# Sheet_HTN.net
KiCad netlist of a schematic drawn in Altium Designer
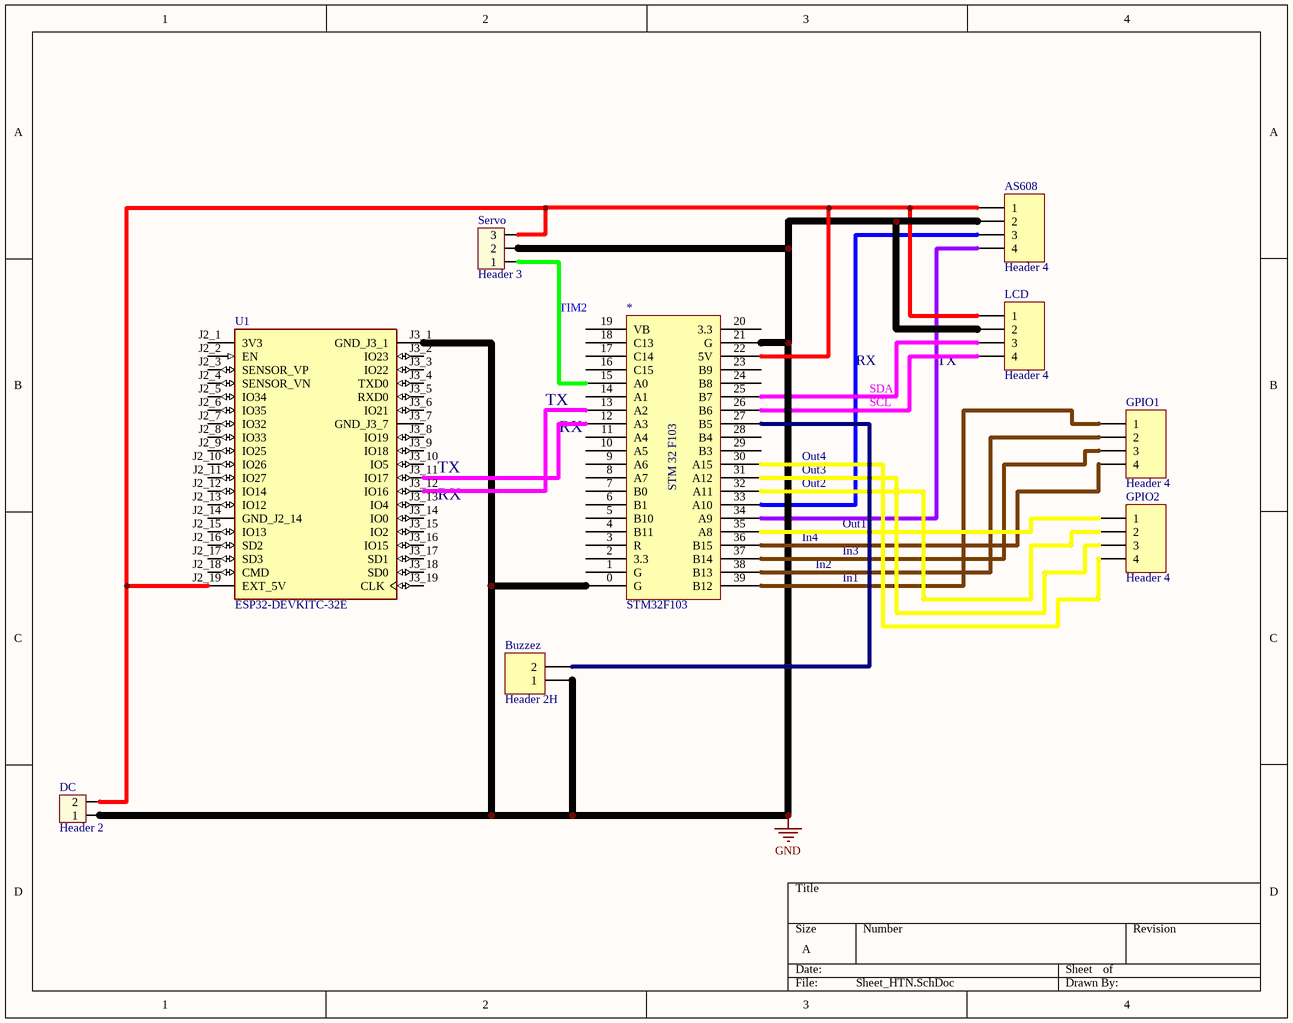
[diagram p0: Sheet_HTN.SchDoc]

(export (version "E")
  (design (tool "Eeschema 10.0.6"))
  (components
    (comp (ref "*")
      (value "STM32F103")
      (footprint "STM32F103")
      (libsource (lib "syhaunguyen__1") (part "STM32F103"))
    )
    (comp (ref "AS608")
      (value "Header 4")
      (footprint "HDR1X4")
      (description "Header, 4-Pin")
      (fields (field (name "PUBLISHER") "Altium Limited"))
      (libsource (lib "minhha") (part "Header 4"))
    )
    (comp (ref "Buzzez")
      (value "Header 2H")
      (footprint "HDR1X2H")
      (description "Header, 2-Pin, Right Angle")
      (fields (field (name "PUBLISHER") "Altium Limited"))
      (libsource (lib "minhha") (part "Header 2H"))
    )
    (comp (ref "DC")
      (value "Header 2")
      (footprint "HED2")
      (description "Header 2 (Green)")
      (libsource (lib "syhaunguyen") (part "Hed2"))
    )
    (comp (ref "GPIO1")
      (value "Header 4")
      (footprint "HDR1X4")
      (description "Header, 4-Pin")
      (fields (field (name "PUBLISHER") "Altium Limited"))
      (libsource (lib "minhha") (part "Header 4"))
    )
    (comp (ref "GPIO2")
      (value "Header 4")
      (footprint "HDR1X4")
      (description "Header, 4-Pin")
      (fields (field (name "PUBLISHER") "Altium Limited"))
      (libsource (lib "minhha") (part "Header 4"))
    )
    (comp (ref "LCD")
      (value "Header 4")
      (footprint "HDR1X4")
      (description "Header, 4-Pin")
      (fields (field (name "PUBLISHER") "Altium Limited"))
      (libsource (lib "minhha") (part "Header 4"))
    )
    (comp (ref "Servo")
      (value "Header 3")
      (footprint "HED3")
      (description "Header 3 (Green)")
      (libsource (lib "syhaunguyen") (part "Hed3"))
    )
    (comp (ref "U1")
      (value "ESP32-DEVKITC-32E")
      (footprint "MODULE_ESP32-DEVKITC-32E")
      (fields (field (name "MF") "Espressif Systems"))
      (libsource (lib "ESP32-DEVKITC-32E") (part "ESP32-DEVKITC-32E"))
    )
  )
  (nets
    (net (code "1") (name "GND") (class "Default")
      (node (ref "*") (pin "0") (pinfunction "G_0") (pintype "passive"))
      (node (ref "*") (pin "21") (pinfunction "G_21") (pintype "passive"))
      (node (ref "AS608") (pin "2") (pinfunction "2_2") (pintype "passive"))
      (node (ref "Buzzez") (pin "1") (pinfunction "1_1") (pintype "passive"))
      (node (ref "DC") (pin "1") (pinfunction "1_1") (pintype "passive"))
      (node (ref "LCD") (pin "2") (pinfunction "2_2") (pintype "passive"))
      (node (ref "Servo") (pin "2") (pinfunction "2_2") (pintype "passive"))
      (node (ref "U1") (pin "J3_1") (pinfunction "GND_J3_1_J3_1") (pintype "power_in"))
    )
    (net (code "2") (name "Net-(*-5V)") (class "Default")
      (node (ref "*") (pin "22") (pinfunction "5V_22") (pintype "passive"))
      (node (ref "AS608") (pin "1") (pinfunction "1_1") (pintype "passive"))
      (node (ref "DC") (pin "2") (pinfunction "2_2") (pintype "passive"))
      (node (ref "LCD") (pin "1") (pinfunction "1_1") (pintype "passive"))
      (node (ref "Servo") (pin "3") (pinfunction "3_3") (pintype "passive"))
      (node (ref "U1") (pin "J2_19") (pinfunction "EXT_5V_J2_19") (pintype "power_in"))
    )
    (net (code "3") (name "Net-(*-A0)") (class "Default")
      (node (ref "*") (pin "15") (pinfunction "A0_15") (pintype "passive"))
      (node (ref "Servo") (pin "1") (pinfunction "1_1") (pintype "passive"))
    )
    (net (code "4") (name "Net-(*-A2)") (class "Default")
      (node (ref "*") (pin "13") (pinfunction "A2_13") (pintype "passive"))
      (node (ref "U1") (pin "J3_12") (pinfunction "IO16_J3_12") (pintype "bidirectional"))
    )
    (net (code "5") (name "Net-(*-A3)") (class "Default")
      (node (ref "*") (pin "12") (pinfunction "A3_12") (pintype "passive"))
      (node (ref "U1") (pin "J3_11") (pinfunction "IO17_J3_11") (pintype "bidirectional"))
    )
    (net (code "6") (name "Net-(*-A8)") (class "Default")
      (node (ref "*") (pin "35") (pinfunction "A8_35") (pintype "passive"))
      (node (ref "GPIO2") (pin "1") (pinfunction "1_1") (pintype "passive"))
    )
    (net (code "7") (name "Net-(*-A9)") (class "Default")
      (node (ref "*") (pin "34") (pinfunction "A9_34") (pintype "passive"))
      (node (ref "AS608") (pin "4") (pinfunction "4_4") (pintype "passive"))
    )
    (net (code "8") (name "Net-(*-A10)") (class "Default")
      (node (ref "*") (pin "33") (pinfunction "A10_33") (pintype "passive"))
      (node (ref "AS608") (pin "3") (pinfunction "3_3") (pintype "passive"))
    )
    (net (code "9") (name "Net-(*-A11)") (class "Default")
      (node (ref "*") (pin "32") (pinfunction "A11_32") (pintype "passive"))
      (node (ref "GPIO2") (pin "2") (pinfunction "2_2") (pintype "passive"))
    )
    (net (code "10") (name "Net-(*-A12)") (class "Default")
      (node (ref "*") (pin "31") (pinfunction "A12_31") (pintype "passive"))
      (node (ref "GPIO2") (pin "3") (pinfunction "3_3") (pintype "passive"))
    )
    (net (code "11") (name "Net-(*-A15)") (class "Default")
      (node (ref "*") (pin "30") (pinfunction "A15_30") (pintype "passive"))
      (node (ref "GPIO2") (pin "4") (pinfunction "4_4") (pintype "passive"))
    )
    (net (code "12") (name "Net-(*-B5)") (class "Default")
      (node (ref "*") (pin "27") (pinfunction "B5_27") (pintype "passive"))
      (node (ref "Buzzez") (pin "2") (pinfunction "2_2") (pintype "passive"))
    )
    (net (code "13") (name "Net-(*-B6)") (class "Default")
      (node (ref "*") (pin "26") (pinfunction "B6_26") (pintype "passive"))
      (node (ref "LCD") (pin "4") (pinfunction "4_4") (pintype "passive"))
    )
    (net (code "14") (name "Net-(*-B7)") (class "Default")
      (node (ref "*") (pin "25") (pinfunction "B7_25") (pintype "passive"))
      (node (ref "LCD") (pin "3") (pinfunction "3_3") (pintype "passive"))
    )
    (net (code "15") (name "Net-(*-B12)") (class "Default")
      (node (ref "*") (pin "39") (pinfunction "B12_39") (pintype "passive"))
      (node (ref "GPIO1") (pin "1") (pinfunction "1_1") (pintype "passive"))
    )
    (net (code "16") (name "Net-(*-B13)") (class "Default")
      (node (ref "*") (pin "38") (pinfunction "B13_38") (pintype "passive"))
      (node (ref "GPIO1") (pin "2") (pinfunction "2_2") (pintype "passive"))
    )
    (net (code "17") (name "Net-(*-B14)") (class "Default")
      (node (ref "*") (pin "37") (pinfunction "B14_37") (pintype "passive"))
      (node (ref "GPIO1") (pin "3") (pinfunction "3_3") (pintype "passive"))
    )
    (net (code "18") (name "Net-(*-B15)") (class "Default")
      (node (ref "*") (pin "36") (pinfunction "B15_36") (pintype "passive"))
      (node (ref "GPIO1") (pin "4") (pinfunction "4_4") (pintype "passive"))
    )
    (net (code "19") (name "unconnected-(*-3.3-Pad2)") (class "Default")
      (node (ref "*") (pin "2") (pinfunction "3.3_2") (pintype "passive"))
    )
    (net (code "20") (name "unconnected-(*-3.3-Pad20)") (class "Default")
      (node (ref "*") (pin "20") (pinfunction "3.3_20") (pintype "passive"))
    )
    (net (code "21") (name "unconnected-(*-A1-Pad14)") (class "Default")
      (node (ref "*") (pin "14") (pinfunction "A1_14") (pintype "passive"))
    )
    (net (code "22") (name "unconnected-(*-A4-Pad11)") (class "Default")
      (node (ref "*") (pin "11") (pinfunction "A4_11") (pintype "passive"))
    )
    (net (code "23") (name "unconnected-(*-A5-Pad10)") (class "Default")
      (node (ref "*") (pin "10") (pinfunction "A5_10") (pintype "passive"))
    )
    (net (code "24") (name "unconnected-(*-A6-Pad9)") (class "Default")
      (node (ref "*") (pin "9") (pinfunction "A6_9") (pintype "passive"))
    )
    (net (code "25") (name "unconnected-(*-A7-Pad8)") (class "Default")
      (node (ref "*") (pin "8") (pinfunction "A7_8") (pintype "passive"))
    )
    (net (code "26") (name "unconnected-(*-B0-Pad7)") (class "Default")
      (node (ref "*") (pin "7") (pinfunction "B0_7") (pintype "passive"))
    )
    (net (code "27") (name "unconnected-(*-B1-Pad6)") (class "Default")
      (node (ref "*") (pin "6") (pinfunction "B1_6") (pintype "passive"))
    )
    (net (code "28") (name "unconnected-(*-B3-Pad29)") (class "Default")
      (node (ref "*") (pin "29") (pinfunction "B3_29") (pintype "passive"))
    )
    (net (code "29") (name "unconnected-(*-B4-Pad28)") (class "Default")
      (node (ref "*") (pin "28") (pinfunction "B4_28") (pintype "passive"))
    )
    (net (code "30") (name "unconnected-(*-B8-Pad24)") (class "Default")
      (node (ref "*") (pin "24") (pinfunction "B8_24") (pintype "passive"))
    )
    (net (code "31") (name "unconnected-(*-B9-Pad23)") (class "Default")
      (node (ref "*") (pin "23") (pinfunction "B9_23") (pintype "passive"))
    )
    (net (code "32") (name "unconnected-(*-B10-Pad5)") (class "Default")
      (node (ref "*") (pin "5") (pinfunction "B10_5") (pintype "passive"))
    )
    (net (code "33") (name "unconnected-(*-B11-Pad4)") (class "Default")
      (node (ref "*") (pin "4") (pinfunction "B11_4") (pintype "passive"))
    )
    (net (code "34") (name "unconnected-(*-C13-Pad18)") (class "Default")
      (node (ref "*") (pin "18") (pinfunction "C13_18") (pintype "passive"))
    )
    (net (code "35") (name "unconnected-(*-C14-Pad17)") (class "Default")
      (node (ref "*") (pin "17") (pinfunction "C14_17") (pintype "passive"))
    )
    (net (code "36") (name "unconnected-(*-C15-Pad16)") (class "Default")
      (node (ref "*") (pin "16") (pinfunction "C15_16") (pintype "passive"))
    )
    (net (code "37") (name "unconnected-(*-G-Pad1)") (class "Default")
      (node (ref "*") (pin "1") (pinfunction "G_1") (pintype "passive"))
    )
    (net (code "38") (name "unconnected-(*-R-Pad3)") (class "Default")
      (node (ref "*") (pin "3") (pinfunction "R_3") (pintype "passive"))
    )
    (net (code "39") (name "unconnected-(*-VB-Pad19)") (class "Default")
      (node (ref "*") (pin "19") (pinfunction "VB_19") (pintype "passive"))
    )
    (net (code "40") (name "unconnected-(U1-3V3-PadJ2_1)") (class "Default")
      (node (ref "U1") (pin "J2_1") (pinfunction "3V3_J2_1") (pintype "power_in"))
    )
    (net (code "41") (name "unconnected-(U1-CLK-PadJ3_19)") (class "Default")
      (node (ref "U1") (pin "J3_19") (pinfunction "CLK_J3_19") (pintype "bidirectional"))
    )
    (net (code "42") (name "unconnected-(U1-CMD-PadJ2_18)") (class "Default")
      (node (ref "U1") (pin "J2_18") (pinfunction "CMD_J2_18") (pintype "bidirectional"))
    )
    (net (code "43") (name "unconnected-(U1-EN-PadJ2_2)") (class "Default")
      (node (ref "U1") (pin "J2_2") (pinfunction "EN_J2_2") (pintype "input"))
    )
    (net (code "44") (name "unconnected-(U1-GND_J2_14-PadJ2_14)") (class "Default")
      (node (ref "U1") (pin "J2_14") (pinfunction "GND_J2_14_J2_14") (pintype "power_in"))
    )
    (net (code "45") (name "unconnected-(U1-GND_J3_7-PadJ3_7)") (class "Default")
      (node (ref "U1") (pin "J3_7") (pinfunction "GND_J3_7_J3_7") (pintype "power_in"))
    )
    (net (code "46") (name "unconnected-(U1-IO0-PadJ3_14)") (class "Default")
      (node (ref "U1") (pin "J3_14") (pinfunction "IO0_J3_14") (pintype "bidirectional"))
    )
    (net (code "47") (name "unconnected-(U1-IO2-PadJ3_15)") (class "Default")
      (node (ref "U1") (pin "J3_15") (pinfunction "IO2_J3_15") (pintype "bidirectional"))
    )
    (net (code "48") (name "unconnected-(U1-IO4-PadJ3_13)") (class "Default")
      (node (ref "U1") (pin "J3_13") (pinfunction "IO4_J3_13") (pintype "bidirectional"))
    )
    (net (code "49") (name "unconnected-(U1-IO5-PadJ3_10)") (class "Default")
      (node (ref "U1") (pin "J3_10") (pinfunction "IO5_J3_10") (pintype "bidirectional"))
    )
    (net (code "50") (name "unconnected-(U1-IO12-PadJ2_13)") (class "Default")
      (node (ref "U1") (pin "J2_13") (pinfunction "IO12_J2_13") (pintype "bidirectional"))
    )
    (net (code "51") (name "unconnected-(U1-IO13-PadJ2_15)") (class "Default")
      (node (ref "U1") (pin "J2_15") (pinfunction "IO13_J2_15") (pintype "bidirectional"))
    )
    (net (code "52") (name "unconnected-(U1-IO14-PadJ2_12)") (class "Default")
      (node (ref "U1") (pin "J2_12") (pinfunction "IO14_J2_12") (pintype "bidirectional"))
    )
    (net (code "53") (name "unconnected-(U1-IO15-PadJ3_16)") (class "Default")
      (node (ref "U1") (pin "J3_16") (pinfunction "IO15_J3_16") (pintype "bidirectional"))
    )
    (net (code "54") (name "unconnected-(U1-IO18-PadJ3_9)") (class "Default")
      (node (ref "U1") (pin "J3_9") (pinfunction "IO18_J3_9") (pintype "bidirectional"))
    )
    (net (code "55") (name "unconnected-(U1-IO19-PadJ3_8)") (class "Default")
      (node (ref "U1") (pin "J3_8") (pinfunction "IO19_J3_8") (pintype "bidirectional"))
    )
    (net (code "56") (name "unconnected-(U1-IO21-PadJ3_6)") (class "Default")
      (node (ref "U1") (pin "J3_6") (pinfunction "IO21_J3_6") (pintype "bidirectional"))
    )
    (net (code "57") (name "unconnected-(U1-IO22-PadJ3_3)") (class "Default")
      (node (ref "U1") (pin "J3_3") (pinfunction "IO22_J3_3") (pintype "bidirectional"))
    )
    (net (code "58") (name "unconnected-(U1-IO23-PadJ3_2)") (class "Default")
      (node (ref "U1") (pin "J3_2") (pinfunction "IO23_J3_2") (pintype "bidirectional"))
    )
    (net (code "59") (name "unconnected-(U1-IO25-PadJ2_9)") (class "Default")
      (node (ref "U1") (pin "J2_9") (pinfunction "IO25_J2_9") (pintype "bidirectional"))
    )
    (net (code "60") (name "unconnected-(U1-IO26-PadJ2_10)") (class "Default")
      (node (ref "U1") (pin "J2_10") (pinfunction "IO26_J2_10") (pintype "bidirectional"))
    )
    (net (code "61") (name "unconnected-(U1-IO27-PadJ2_11)") (class "Default")
      (node (ref "U1") (pin "J2_11") (pinfunction "IO27_J2_11") (pintype "bidirectional"))
    )
    (net (code "62") (name "unconnected-(U1-IO32-PadJ2_7)") (class "Default")
      (node (ref "U1") (pin "J2_7") (pinfunction "IO32_J2_7") (pintype "bidirectional"))
    )
    (net (code "63") (name "unconnected-(U1-IO33-PadJ2_8)") (class "Default")
      (node (ref "U1") (pin "J2_8") (pinfunction "IO33_J2_8") (pintype "bidirectional"))
    )
    (net (code "64") (name "unconnected-(U1-IO34-PadJ2_5)") (class "Default")
      (node (ref "U1") (pin "J2_5") (pinfunction "IO34_J2_5") (pintype "bidirectional"))
    )
    (net (code "65") (name "unconnected-(U1-IO35-PadJ2_6)") (class "Default")
      (node (ref "U1") (pin "J2_6") (pinfunction "IO35_J2_6") (pintype "bidirectional"))
    )
    (net (code "66") (name "unconnected-(U1-RXD0-PadJ3_5)") (class "Default")
      (node (ref "U1") (pin "J3_5") (pinfunction "RXD0_J3_5") (pintype "bidirectional"))
    )
    (net (code "67") (name "unconnected-(U1-SD0-PadJ3_18)") (class "Default")
      (node (ref "U1") (pin "J3_18") (pinfunction "SD0_J3_18") (pintype "bidirectional"))
    )
    (net (code "68") (name "unconnected-(U1-SD1-PadJ3_17)") (class "Default")
      (node (ref "U1") (pin "J3_17") (pinfunction "SD1_J3_17") (pintype "bidirectional"))
    )
    (net (code "69") (name "unconnected-(U1-SD2-PadJ2_16)") (class "Default")
      (node (ref "U1") (pin "J2_16") (pinfunction "SD2_J2_16") (pintype "bidirectional"))
    )
    (net (code "70") (name "unconnected-(U1-SD3-PadJ2_17)") (class "Default")
      (node (ref "U1") (pin "J2_17") (pinfunction "SD3_J2_17") (pintype "bidirectional"))
    )
    (net (code "71") (name "unconnected-(U1-SENSOR_VN-PadJ2_4)") (class "Default")
      (node (ref "U1") (pin "J2_4") (pinfunction "SENSOR_VN_J2_4") (pintype "bidirectional"))
    )
    (net (code "72") (name "unconnected-(U1-SENSOR_VP-PadJ2_3)") (class "Default")
      (node (ref "U1") (pin "J2_3") (pinfunction "SENSOR_VP_J2_3") (pintype "bidirectional"))
    )
    (net (code "73") (name "unconnected-(U1-TXD0-PadJ3_4)") (class "Default")
      (node (ref "U1") (pin "J3_4") (pinfunction "TXD0_J3_4") (pintype "bidirectional"))
    )
  )
)
